# AK4558EN_Breakout.net
KiCad netlist of a schematic drawn in EAGLE
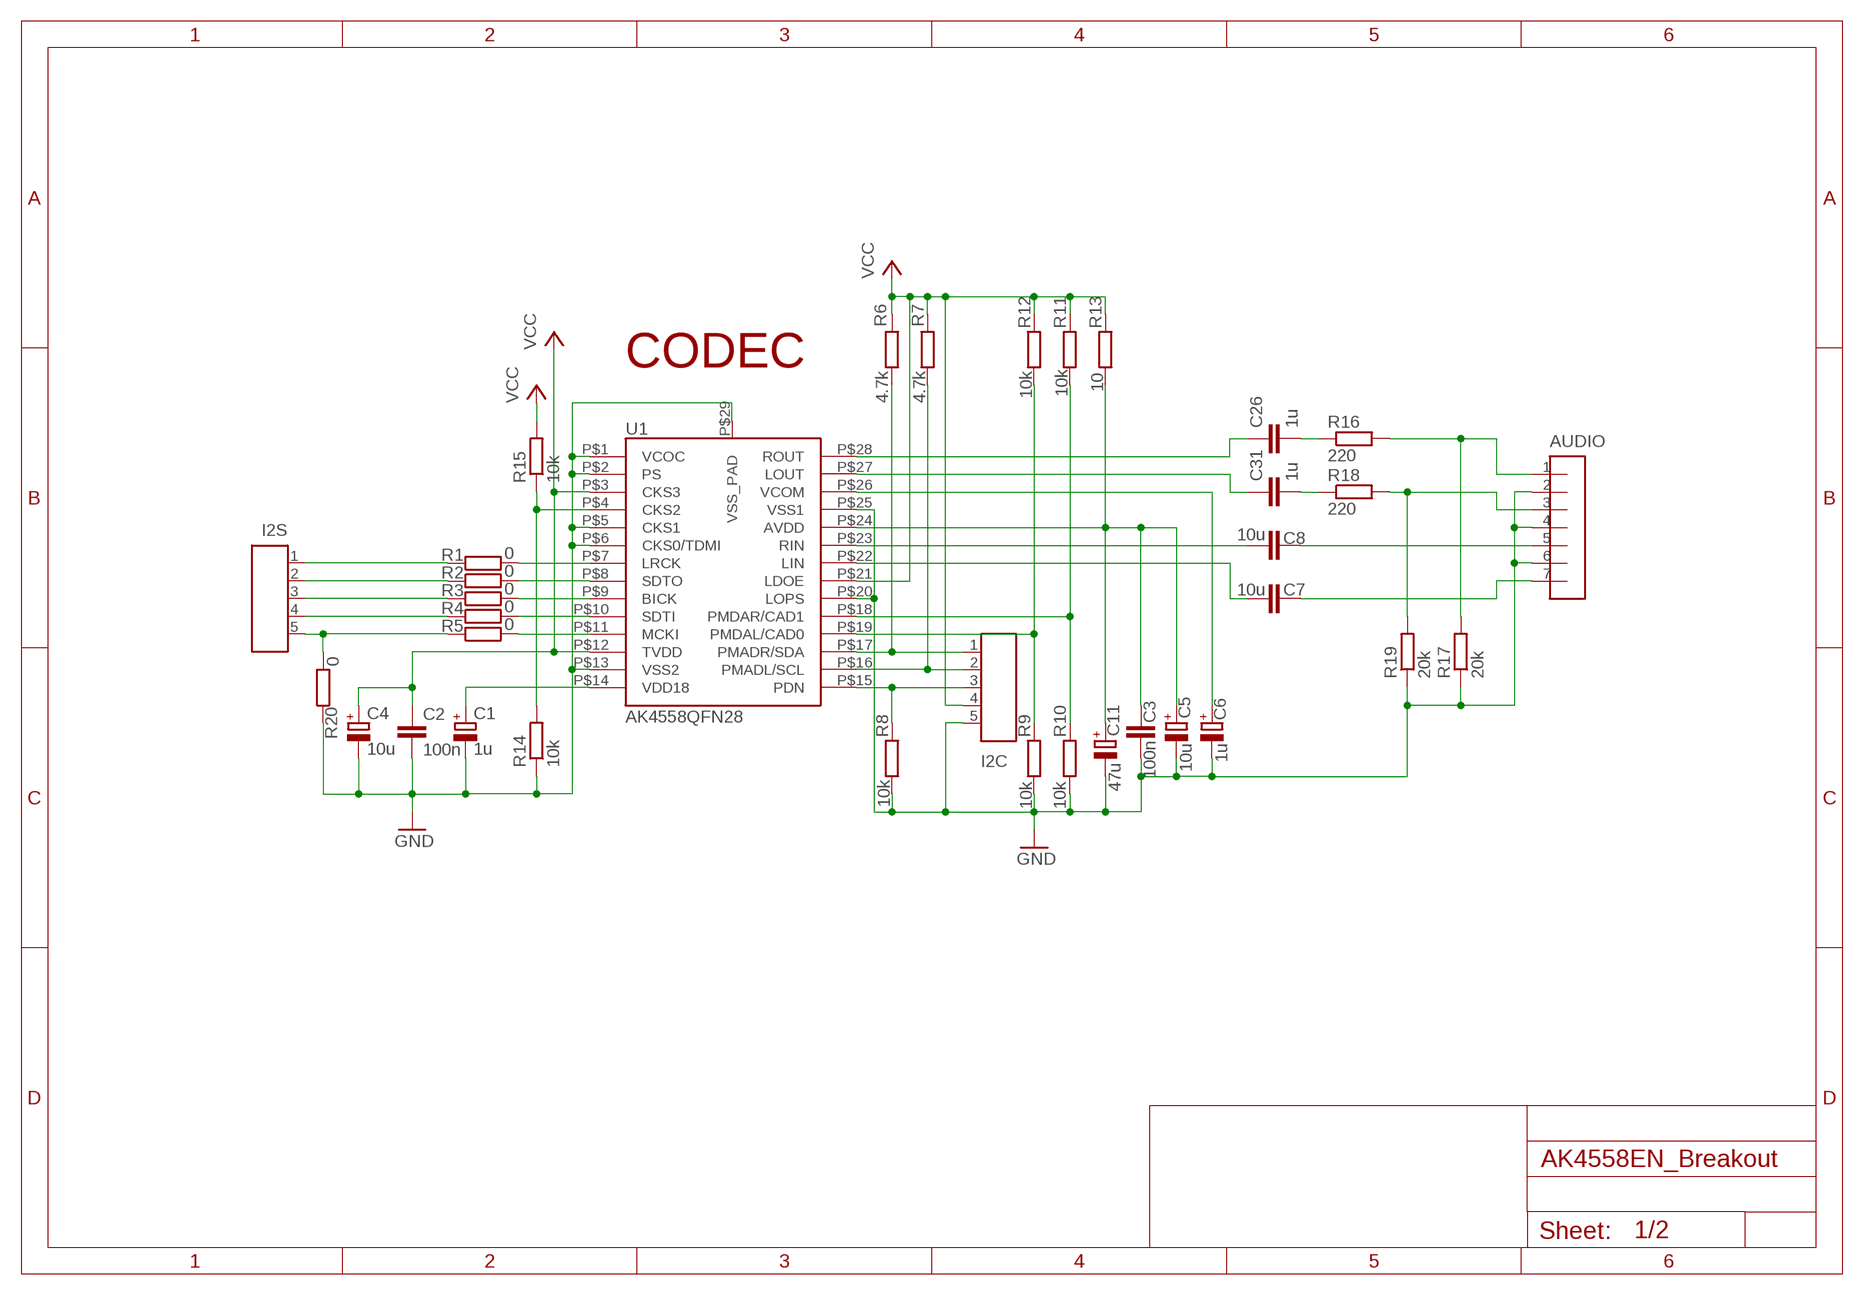
[diagram p0: schematic, sheet 1]
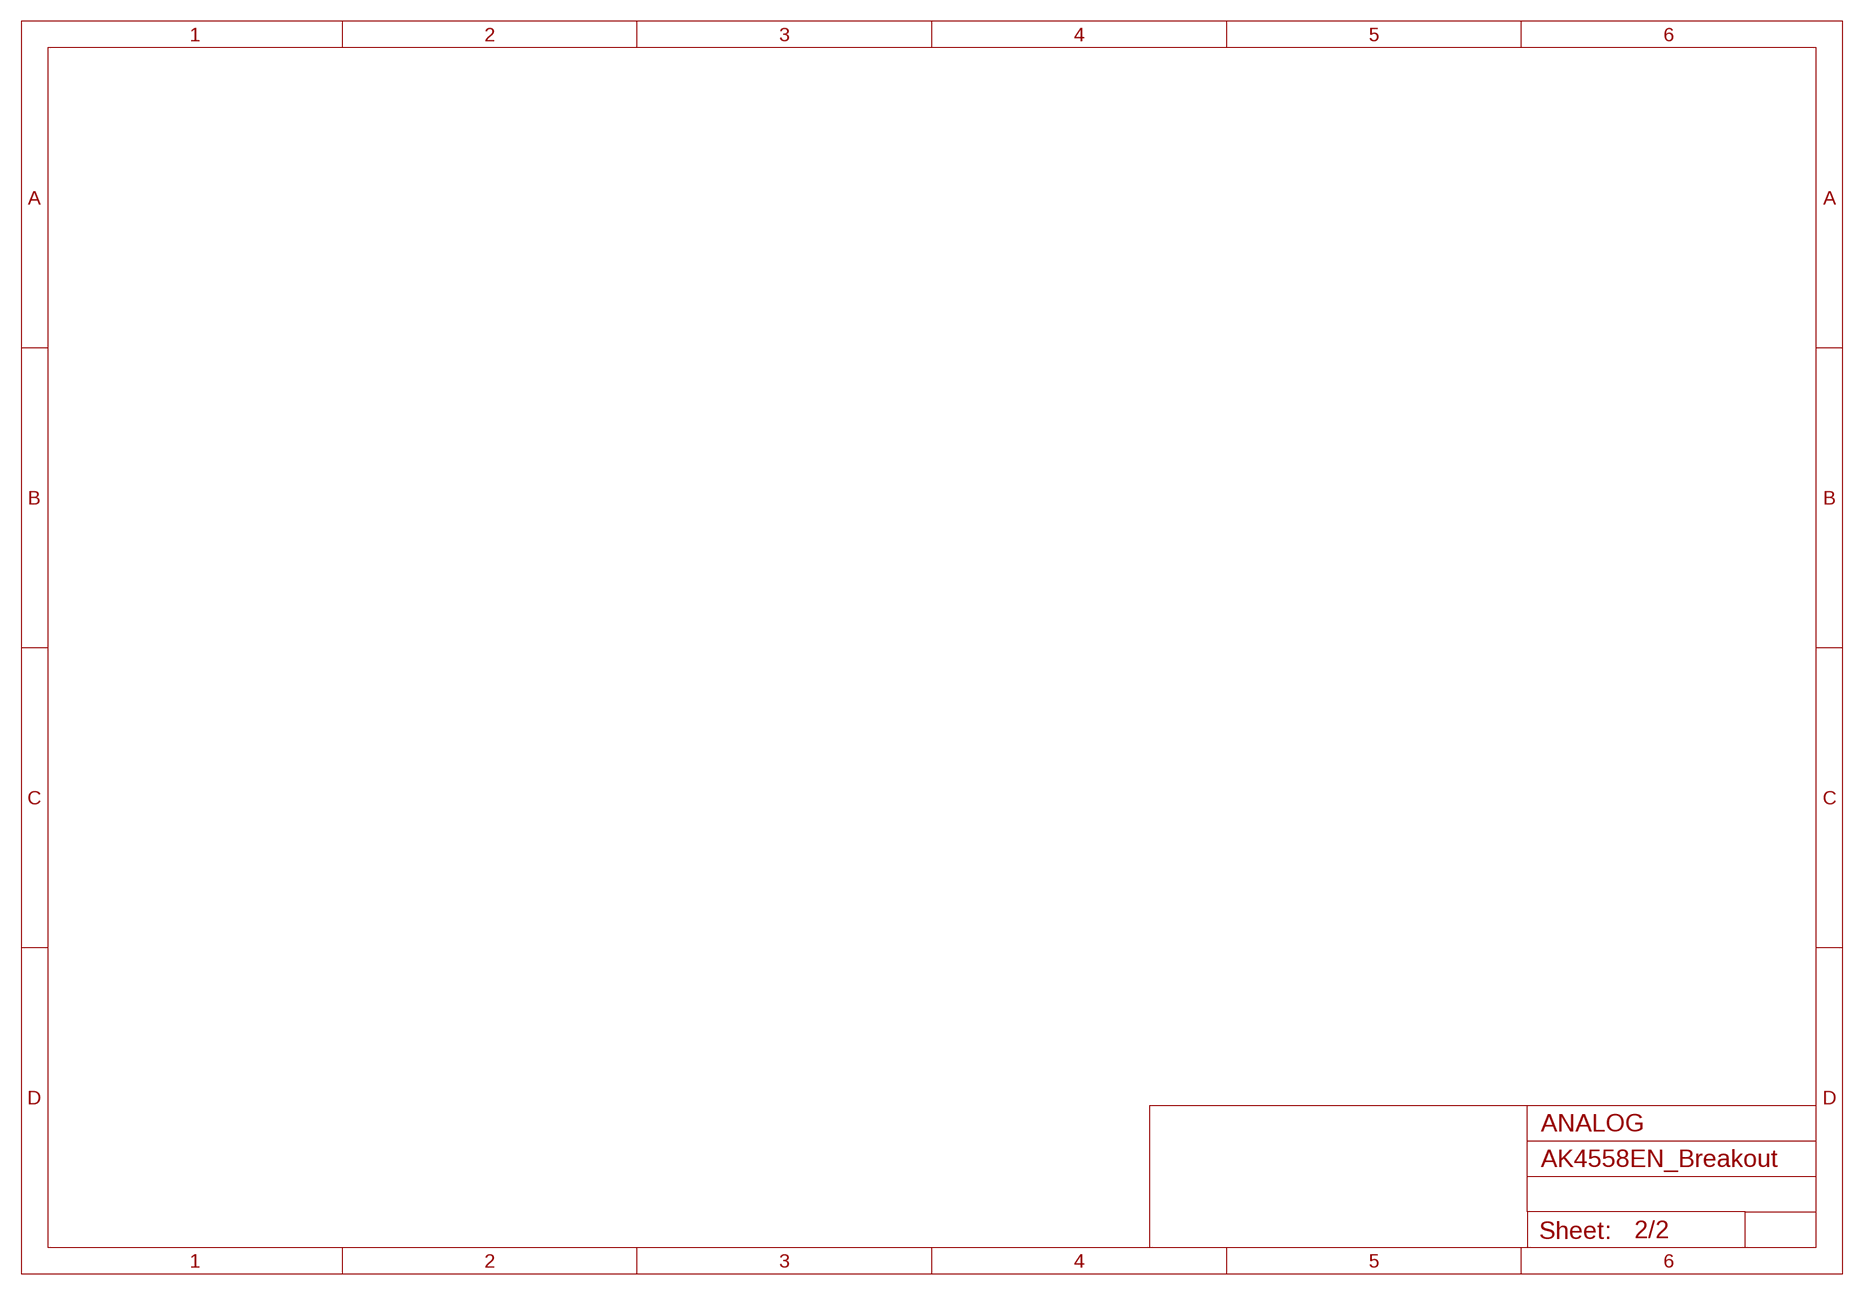
[diagram p1: schematic, sheet 2]

(export (version "E")
  (design (tool "Eeschema 10.0.6"))
  (components
    (comp (ref "AUDIO")
      (value "PH_ST_7")
      (footprint "eagle-import:HDRV7W64P254_1X7_1016X508X838B")
      (libsource (lib "eagle-import") (part "PH_ST_7"))
    )
    (comp (ref "C1")
      (value "1u")
      (footprint "eagle-import:SMC_A")
      (libsource (lib "eagle-import") (part "CPOL-EUSMCA"))
    )
    (comp (ref "C2")
      (value "100n")
      (footprint "eagle-import:C0603")
      (libsource (lib "eagle-import") (part "C-EUC0603"))
    )
    (comp (ref "C3")
      (value "100n")
      (footprint "eagle-import:C0603")
      (libsource (lib "eagle-import") (part "C-EUC0603"))
    )
    (comp (ref "C4")
      (value "10u")
      (footprint "eagle-import:SMC_B")
      (libsource (lib "eagle-import") (part "CPOL-EUSMCB"))
    )
    (comp (ref "C5")
      (value "10u")
      (footprint "eagle-import:SMC_B")
      (libsource (lib "eagle-import") (part "CPOL-EUSMCB"))
    )
    (comp (ref "C6")
      (value "1u")
      (footprint "eagle-import:SMC_A")
      (libsource (lib "eagle-import") (part "CPOL-EUSMCA"))
    )
    (comp (ref "C7")
      (value "10u")
      (footprint "eagle-import:C0603")
      (libsource (lib "eagle-import") (part "C-EUC0603"))
    )
    (comp (ref "C8")
      (value "10u")
      (footprint "eagle-import:C0603")
      (libsource (lib "eagle-import") (part "C-EUC0603"))
    )
    (comp (ref "C11")
      (value "47u")
      (footprint "eagle-import:SMC_C")
      (libsource (lib "eagle-import") (part "CPOL-EUSMCC"))
    )
    (comp (ref "C26")
      (value "1u")
      (footprint "eagle-import:C0603")
      (libsource (lib "eagle-import") (part "C-EUC0603"))
    )
    (comp (ref "C31")
      (value "1u")
      (footprint "eagle-import:C0603")
      (libsource (lib "eagle-import") (part "C-EUC0603"))
    )
    (comp (ref "I2C")
      (value "PH_ST_5")
      (footprint "eagle-import:HDRV5W64P254_1X5_1016X508X838B")
      (libsource (lib "eagle-import") (part "PH_ST_5"))
    )
    (comp (ref "I2S")
      (value "PH_ST_5")
      (footprint "eagle-import:HDRV5W64P254_1X5_1016X508X838B")
      (libsource (lib "eagle-import") (part "PH_ST_5"))
    )
    (comp (ref "R1")
      (value "0")
      (footprint "eagle-import:R0603")
      (libsource (lib "eagle-import") (part "R-EU_R0603"))
    )
    (comp (ref "R2")
      (value "0")
      (footprint "eagle-import:R0603")
      (libsource (lib "eagle-import") (part "R-EU_R0603"))
    )
    (comp (ref "R3")
      (value "0")
      (footprint "eagle-import:R0603")
      (libsource (lib "eagle-import") (part "R-EU_R0603"))
    )
    (comp (ref "R4")
      (value "0")
      (footprint "eagle-import:R0603")
      (libsource (lib "eagle-import") (part "R-EU_R0603"))
    )
    (comp (ref "R5")
      (value "0")
      (footprint "eagle-import:R0603")
      (libsource (lib "eagle-import") (part "R-EU_R0603"))
    )
    (comp (ref "R6")
      (value "4.7k")
      (footprint "eagle-import:R0603")
      (libsource (lib "eagle-import") (part "R-EU_R0603"))
    )
    (comp (ref "R7")
      (value "4.7k")
      (footprint "eagle-import:R0603")
      (libsource (lib "eagle-import") (part "R-EU_R0603"))
    )
    (comp (ref "R8")
      (value "10k")
      (footprint "eagle-import:R0603")
      (libsource (lib "eagle-import") (part "R-EU_R0603"))
    )
    (comp (ref "R9")
      (value "10k")
      (footprint "eagle-import:R0603")
      (libsource (lib "eagle-import") (part "R-EU_R0603"))
    )
    (comp (ref "R10")
      (value "10k")
      (footprint "eagle-import:R0603")
      (libsource (lib "eagle-import") (part "R-EU_R0603"))
    )
    (comp (ref "R11")
      (value "10k")
      (footprint "eagle-import:R0603")
      (libsource (lib "eagle-import") (part "R-EU_R0603"))
    )
    (comp (ref "R12")
      (value "10k")
      (footprint "eagle-import:R0603")
      (libsource (lib "eagle-import") (part "R-EU_R0603"))
    )
    (comp (ref "R13")
      (value "10")
      (footprint "eagle-import:R0603")
      (libsource (lib "eagle-import") (part "R-EU_R0603"))
    )
    (comp (ref "R14")
      (value "10k")
      (footprint "eagle-import:R0603")
      (libsource (lib "eagle-import") (part "R-EU_R0603"))
    )
    (comp (ref "R15")
      (value "10k")
      (footprint "eagle-import:R0603")
      (libsource (lib "eagle-import") (part "R-EU_R0603"))
    )
    (comp (ref "R16")
      (value "220")
      (footprint "eagle-import:R0603")
      (libsource (lib "eagle-import") (part "R-EU_R0603"))
    )
    (comp (ref "R17")
      (value "20k")
      (footprint "eagle-import:R0603")
      (libsource (lib "eagle-import") (part "R-EU_R0603"))
    )
    (comp (ref "R18")
      (value "220")
      (footprint "eagle-import:R0603")
      (libsource (lib "eagle-import") (part "R-EU_R0603"))
    )
    (comp (ref "R19")
      (value "20k")
      (footprint "eagle-import:R0603")
      (libsource (lib "eagle-import") (part "R-EU_R0603"))
    )
    (comp (ref "R20")
      (value "0")
      (footprint "eagle-import:R0603")
      (libsource (lib "eagle-import") (part "R-EU_R0603"))
    )
    (comp (ref "U1")
      (value "AK4558QFN28")
      (footprint "eagle-import:QFN28_5X5")
      (libsource (lib "eagle-import") (part "AK4558QFN28"))
    )
  )
  (nets
    (net (code "1") (name "GND") (class "Default")
      (node (ref "AUDIO") (pin "2") (pinfunction "P$2_2") (pintype "bidirectional"))
      (node (ref "AUDIO") (pin "4") (pinfunction "P$4_4") (pintype "bidirectional"))
      (node (ref "AUDIO") (pin "6") (pinfunction "P$6_6") (pintype "bidirectional"))
      (node (ref "C1") (pin "-") (pinfunction "-_-") (pintype "passive"))
      (node (ref "C11") (pin "-") (pinfunction "-_-") (pintype "passive"))
      (node (ref "C2") (pin "2") (pinfunction "2_2") (pintype "passive"))
      (node (ref "C3") (pin "2") (pinfunction "2_2") (pintype "passive"))
      (node (ref "C4") (pin "-") (pinfunction "-_-") (pintype "passive"))
      (node (ref "C5") (pin "-") (pinfunction "-_-") (pintype "passive"))
      (node (ref "C6") (pin "-") (pinfunction "-_-") (pintype "passive"))
      (node (ref "I2C") (pin "5") (pinfunction "P$9_5") (pintype "bidirectional"))
      (node (ref "R10") (pin "1") (pinfunction "1_1") (pintype "passive"))
      (node (ref "R14") (pin "1") (pinfunction "1_1") (pintype "passive"))
      (node (ref "R17") (pin "1") (pinfunction "1_1") (pintype "passive"))
      (node (ref "R19") (pin "1") (pinfunction "1_1") (pintype "passive"))
      (node (ref "R20") (pin "1") (pinfunction "1_1") (pintype "passive"))
      (node (ref "R8") (pin "1") (pinfunction "1_1") (pintype "passive"))
      (node (ref "R9") (pin "1") (pinfunction "1_1") (pintype "passive"))
      (node (ref "U1") (pin "P$1") (pinfunction "VCOC_P$1") (pintype "bidirectional"))
      (node (ref "U1") (pin "P$13") (pinfunction "VSS2_P$13") (pintype "bidirectional"))
      (node (ref "U1") (pin "P$2") (pinfunction "PS_P$2") (pintype "bidirectional"))
      (node (ref "U1") (pin "P$20") (pinfunction "LOPS_P$20") (pintype "bidirectional"))
      (node (ref "U1") (pin "P$25") (pinfunction "VSS1_P$25") (pintype "bidirectional"))
      (node (ref "U1") (pin "P$29") (pinfunction "VSS_PAD_P$29") (pintype "bidirectional"))
      (node (ref "U1") (pin "P$5") (pinfunction "CKS1_P$5") (pintype "bidirectional"))
      (node (ref "U1") (pin "P$6") (pinfunction "CKS0/TDMI_P$6") (pintype "bidirectional"))
    )
    (net (code "2") (name "Net-(AUDIO-P$1)") (class "Default")
      (node (ref "AUDIO") (pin "1") (pinfunction "P$1_1") (pintype "bidirectional"))
      (node (ref "R16") (pin "2") (pinfunction "2_2") (pintype "passive"))
      (node (ref "R17") (pin "2") (pinfunction "2_2") (pintype "passive"))
    )
    (net (code "3") (name "Net-(AUDIO-P$3)") (class "Default")
      (node (ref "AUDIO") (pin "3") (pinfunction "P$3_3") (pintype "bidirectional"))
      (node (ref "R18") (pin "2") (pinfunction "2_2") (pintype "passive"))
      (node (ref "R19") (pin "2") (pinfunction "2_2") (pintype "passive"))
    )
    (net (code "4") (name "Net-(AUDIO-P$5)") (class "Default")
      (node (ref "AUDIO") (pin "5") (pinfunction "P$5_5") (pintype "bidirectional"))
      (node (ref "C8") (pin "1") (pinfunction "1_1") (pintype "passive"))
    )
    (net (code "5") (name "Net-(AUDIO-P$7)") (class "Default")
      (node (ref "AUDIO") (pin "7") (pinfunction "P$7_7") (pintype "bidirectional"))
      (node (ref "C7") (pin "1") (pinfunction "1_1") (pintype "passive"))
    )
    (net (code "6") (name "Net-(C26-Pad2)") (class "Default")
      (node (ref "C26") (pin "2") (pinfunction "2_2") (pintype "passive"))
      (node (ref "R16") (pin "1") (pinfunction "1_1") (pintype "passive"))
    )
    (net (code "7") (name "Net-(C31-Pad2)") (class "Default")
      (node (ref "C31") (pin "2") (pinfunction "2_2") (pintype "passive"))
      (node (ref "R18") (pin "1") (pinfunction "1_1") (pintype "passive"))
    )
    (net (code "8") (name "Net-(I2C-P$1)") (class "Default")
      (node (ref "I2C") (pin "1") (pinfunction "P$1_1") (pintype "bidirectional"))
      (node (ref "R6") (pin "1") (pinfunction "1_1") (pintype "passive"))
      (node (ref "U1") (pin "P$17") (pinfunction "PMADR/SDA_P$17") (pintype "bidirectional"))
    )
    (net (code "9") (name "Net-(I2C-P$3)") (class "Default")
      (node (ref "I2C") (pin "2") (pinfunction "P$3_2") (pintype "bidirectional"))
      (node (ref "R7") (pin "1") (pinfunction "1_1") (pintype "passive"))
      (node (ref "U1") (pin "P$16") (pinfunction "PMADL/SCL_P$16") (pintype "bidirectional"))
    )
    (net (code "10") (name "Net-(I2C-P$5)") (class "Default")
      (node (ref "I2C") (pin "3") (pinfunction "P$5_3") (pintype "bidirectional"))
      (node (ref "R8") (pin "2") (pinfunction "2_2") (pintype "passive"))
      (node (ref "U1") (pin "P$15") (pinfunction "PDN_P$15") (pintype "bidirectional"))
    )
    (net (code "11") (name "Net-(I2S-P$1)") (class "Default")
      (node (ref "I2S") (pin "1") (pinfunction "P$1_1") (pintype "bidirectional"))
      (node (ref "R1") (pin "1") (pinfunction "1_1") (pintype "passive"))
    )
    (net (code "12") (name "Net-(I2S-P$3)") (class "Default")
      (node (ref "I2S") (pin "2") (pinfunction "P$3_2") (pintype "bidirectional"))
      (node (ref "R2") (pin "1") (pinfunction "1_1") (pintype "passive"))
    )
    (net (code "13") (name "Net-(I2S-P$5)") (class "Default")
      (node (ref "I2S") (pin "3") (pinfunction "P$5_3") (pintype "bidirectional"))
      (node (ref "R3") (pin "1") (pinfunction "1_1") (pintype "passive"))
    )
    (net (code "14") (name "Net-(I2S-P$7)") (class "Default")
      (node (ref "I2S") (pin "4") (pinfunction "P$7_4") (pintype "bidirectional"))
      (node (ref "R4") (pin "1") (pinfunction "1_1") (pintype "passive"))
    )
    (net (code "15") (name "Net-(I2S-P$9)") (class "Default")
      (node (ref "I2S") (pin "5") (pinfunction "P$9_5") (pintype "bidirectional"))
      (node (ref "R20") (pin "2") (pinfunction "2_2") (pintype "passive"))
      (node (ref "R5") (pin "1") (pinfunction "1_1") (pintype "passive"))
    )
    (net (code "16") (name "Net-(U1-AVDD)") (class "Default")
      (node (ref "C11") (pin "+") (pinfunction "+_+") (pintype "passive"))
      (node (ref "C3") (pin "1") (pinfunction "1_1") (pintype "passive"))
      (node (ref "C5") (pin "+") (pinfunction "+_+") (pintype "passive"))
      (node (ref "R13") (pin "1") (pinfunction "1_1") (pintype "passive"))
      (node (ref "U1") (pin "P$24") (pinfunction "AVDD_P$24") (pintype "power_in"))
    )
    (net (code "17") (name "Net-(U1-BICK)") (class "Default")
      (node (ref "R3") (pin "2") (pinfunction "2_2") (pintype "passive"))
      (node (ref "U1") (pin "P$9") (pinfunction "BICK_P$9") (pintype "bidirectional"))
    )
    (net (code "18") (name "Net-(U1-CKS2)") (class "Default")
      (node (ref "R14") (pin "2") (pinfunction "2_2") (pintype "passive"))
      (node (ref "R15") (pin "1") (pinfunction "1_1") (pintype "passive"))
      (node (ref "U1") (pin "P$4") (pinfunction "CKS2_P$4") (pintype "bidirectional"))
    )
    (net (code "19") (name "Net-(U1-LIN)") (class "Default")
      (node (ref "C7") (pin "2") (pinfunction "2_2") (pintype "passive"))
      (node (ref "U1") (pin "P$22") (pinfunction "LIN_P$22") (pintype "input"))
    )
    (net (code "20") (name "Net-(U1-LOUT)") (class "Default")
      (node (ref "C31") (pin "1") (pinfunction "1_1") (pintype "passive"))
      (node (ref "U1") (pin "P$27") (pinfunction "LOUT_P$27") (pintype "bidirectional"))
    )
    (net (code "21") (name "Net-(U1-LRCK)") (class "Default")
      (node (ref "R1") (pin "2") (pinfunction "2_2") (pintype "passive"))
      (node (ref "U1") (pin "P$7") (pinfunction "LRCK_P$7") (pintype "bidirectional"))
    )
    (net (code "22") (name "Net-(U1-MCKI)") (class "Default")
      (node (ref "R5") (pin "2") (pinfunction "2_2") (pintype "passive"))
      (node (ref "U1") (pin "P$11") (pinfunction "MCKI_P$11") (pintype "bidirectional"))
    )
    (net (code "23") (name "Net-(U1-PMDAL{slash}CAD0)") (class "Default")
      (node (ref "R12") (pin "1") (pinfunction "1_1") (pintype "passive"))
      (node (ref "R9") (pin "2") (pinfunction "2_2") (pintype "passive"))
      (node (ref "U1") (pin "P$19") (pinfunction "PMDAL/CAD0_P$19") (pintype "bidirectional"))
    )
    (net (code "24") (name "Net-(U1-PMDAR{slash}CAD1)") (class "Default")
      (node (ref "R10") (pin "2") (pinfunction "2_2") (pintype "passive"))
      (node (ref "R11") (pin "1") (pinfunction "1_1") (pintype "passive"))
      (node (ref "U1") (pin "P$18") (pinfunction "PMDAR/CAD1_P$18") (pintype "bidirectional"))
    )
    (net (code "25") (name "Net-(U1-RIN)") (class "Default")
      (node (ref "C8") (pin "2") (pinfunction "2_2") (pintype "passive"))
      (node (ref "U1") (pin "P$23") (pinfunction "RIN_P$23") (pintype "input"))
    )
    (net (code "26") (name "Net-(U1-ROUT)") (class "Default")
      (node (ref "C26") (pin "1") (pinfunction "1_1") (pintype "passive"))
      (node (ref "U1") (pin "P$28") (pinfunction "ROUT_P$28") (pintype "bidirectional"))
    )
    (net (code "27") (name "Net-(U1-SDTI)") (class "Default")
      (node (ref "R4") (pin "2") (pinfunction "2_2") (pintype "passive"))
      (node (ref "U1") (pin "P$10") (pinfunction "SDTI_P$10") (pintype "bidirectional"))
    )
    (net (code "28") (name "Net-(U1-SDTO)") (class "Default")
      (node (ref "R2") (pin "2") (pinfunction "2_2") (pintype "passive"))
      (node (ref "U1") (pin "P$8") (pinfunction "SDTO_P$8") (pintype "bidirectional"))
    )
    (net (code "29") (name "Net-(U1-VCOM)") (class "Default")
      (node (ref "C6") (pin "+") (pinfunction "+_+") (pintype "passive"))
      (node (ref "U1") (pin "P$26") (pinfunction "VCOM_P$26") (pintype "bidirectional"))
    )
    (net (code "30") (name "Net-(U1-VDD18)") (class "Default")
      (node (ref "C1") (pin "+") (pinfunction "+_+") (pintype "passive"))
      (node (ref "U1") (pin "P$14") (pinfunction "VDD18_P$14") (pintype "bidirectional"))
    )
    (net (code "31") (name "VCC") (class "Default")
      (node (ref "C2") (pin "1") (pinfunction "1_1") (pintype "passive"))
      (node (ref "C4") (pin "+") (pinfunction "+_+") (pintype "passive"))
      (node (ref "I2C") (pin "4") (pinfunction "P$7_4") (pintype "bidirectional"))
      (node (ref "R11") (pin "2") (pinfunction "2_2") (pintype "passive"))
      (node (ref "R12") (pin "2") (pinfunction "2_2") (pintype "passive"))
      (node (ref "R13") (pin "2") (pinfunction "2_2") (pintype "passive"))
      (node (ref "R15") (pin "2") (pinfunction "2_2") (pintype "passive"))
      (node (ref "R6") (pin "2") (pinfunction "2_2") (pintype "passive"))
      (node (ref "R7") (pin "2") (pinfunction "2_2") (pintype "passive"))
      (node (ref "U1") (pin "P$12") (pinfunction "TVDD_P$12") (pintype "bidirectional"))
      (node (ref "U1") (pin "P$21") (pinfunction "LDOE_P$21") (pintype "bidirectional"))
      (node (ref "U1") (pin "P$3") (pinfunction "CKS3_P$3") (pintype "bidirectional"))
    )
  )
)
